# radio_jammer.net
KiCad netlist of a schematic drawn in EAGLE
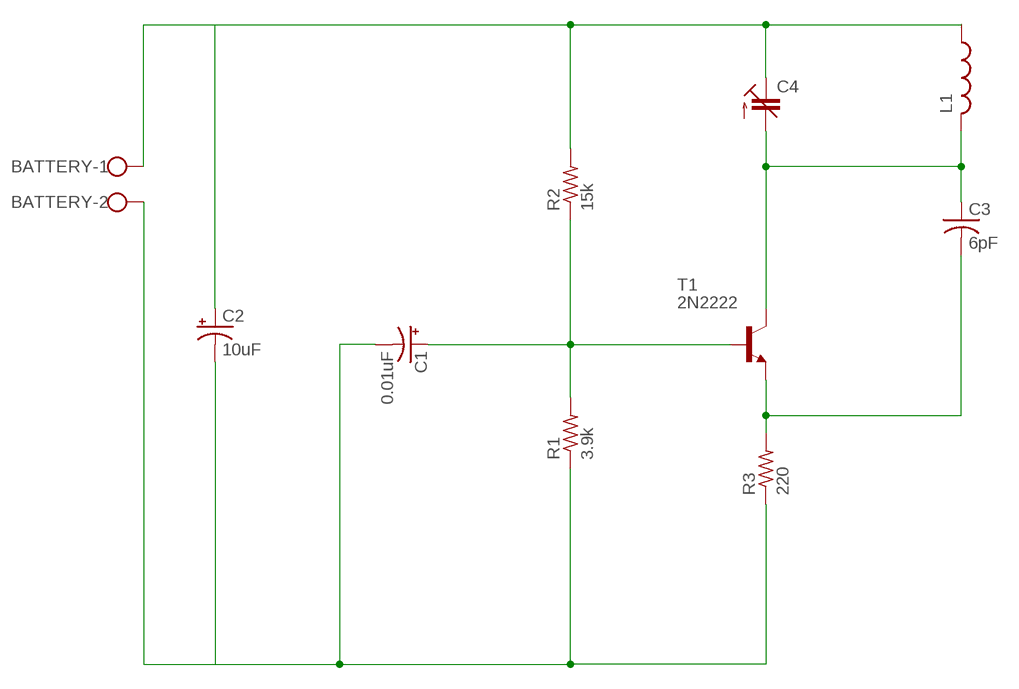
[diagram p0: schematic, sheet 1]

(export (version "E")
  (design (tool "Eeschema 10.0.6"))
  (components
    (comp (ref "BATTERY")
      (value "W237-102")
      (footprint "eagle-import:W237-102")
      (fields (field (name "MPN") "237-102"))
      (libsource (lib "eagle-import") (part "W237-102"))
    )
    (comp (ref "C1")
      (value "0.01uF")
      (footprint "eagle-import:B45181A")
      (libsource (lib "eagle-import") (part "CPOL-USB45181A"))
    )
    (comp (ref "C2")
      (value "10uF")
      (footprint "eagle-import:B45181A")
      (libsource (lib "eagle-import") (part "CPOL-USB45181A"))
    )
    (comp (ref "C3")
      (value "6pF")
      (footprint "eagle-import:C025-025X050")
      (libsource (lib "eagle-import") (part "C-US025-025X050"))
    )
    (comp (ref "C4")
      (value "C-TRIMM3050.504")
      (footprint "eagle-import:CTRIM3050.504")
      (libsource (lib "eagle-import") (part "C-TRIMM3050.504"))
    )
    (comp (ref "L1")
      (value "L-US0204/7")
      (footprint "eagle-import:0204_7")
      (libsource (lib "eagle-import") (part "L-US0204/7"))
    )
    (comp (ref "R1")
      (value "3.9k")
      (footprint "eagle-import:0204_7")
      (libsource (lib "eagle-import") (part "R-US_0204/7"))
    )
    (comp (ref "R2")
      (value "15k")
      (footprint "eagle-import:0204_7")
      (libsource (lib "eagle-import") (part "R-US_0204/7"))
    )
    (comp (ref "R3")
      (value "220")
      (footprint "eagle-import:0204_7")
      (libsource (lib "eagle-import") (part "R-US_0204/7"))
    )
    (comp (ref "T1")
      (value "2N2222")
      (footprint "eagle-import:TO18")
      (libsource (lib "eagle-import") (part "2N2222"))
    )
  )
  (nets
    (net (code "1") (name "Net-(BATTERYA-KL)") (class "Default")
      (node (ref "BATTERY") (pin "1") (pinfunction "KL_1") (pintype "passive"))
      (node (ref "C2") (pin "+") (pinfunction "+_+") (pintype "passive"))
      (node (ref "C4") (pin "1") (pinfunction "E_1") (pintype "passive"))
      (node (ref "L1") (pin "1") (pinfunction "1_1") (pintype "passive"))
      (node (ref "R2") (pin "2") (pinfunction "2_2") (pintype "passive"))
    )
    (net (code "2") (name "Net-(BATTERYB-KL)") (class "Default")
      (node (ref "BATTERY") (pin "2") (pinfunction "KL_2") (pintype "passive"))
      (node (ref "C1") (pin "-") (pinfunction "-_-") (pintype "passive"))
      (node (ref "C2") (pin "-") (pinfunction "-_-") (pintype "passive"))
      (node (ref "R1") (pin "1") (pinfunction "1_1") (pintype "passive"))
      (node (ref "R3") (pin "1") (pinfunction "1_1") (pintype "passive"))
    )
    (net (code "3") (name "Net-(C4-A)") (class "Default")
      (node (ref "C3") (pin "1") (pinfunction "1_1") (pintype "passive"))
      (node (ref "C4") (pin "2") (pinfunction "A_2") (pintype "passive"))
      (node (ref "L1") (pin "2") (pinfunction "2_2") (pintype "passive"))
      (node (ref "T1") (pin "3") (pinfunction "C_3") (pintype "passive"))
    )
    (net (code "4") (name "Net-(T1-B)") (class "Default")
      (node (ref "C1") (pin "+") (pinfunction "+_+") (pintype "passive"))
      (node (ref "R1") (pin "2") (pinfunction "2_2") (pintype "passive"))
      (node (ref "R2") (pin "1") (pinfunction "1_1") (pintype "passive"))
      (node (ref "T1") (pin "2") (pinfunction "B_2") (pintype "passive"))
    )
    (net (code "5") (name "Net-(T1-E)") (class "Default")
      (node (ref "C3") (pin "2") (pinfunction "2_2") (pintype "passive"))
      (node (ref "R3") (pin "2") (pinfunction "2_2") (pintype "passive"))
      (node (ref "T1") (pin "1") (pinfunction "E_1") (pintype "passive"))
    )
  )
)
